# low-pass-fitler.net
KiCad netlist of a schematic drawn in Altium Designer
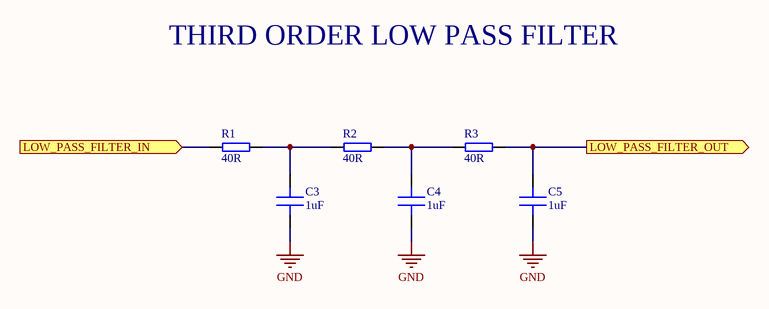
[diagram p0: low-pass-fitler.SchDoc]

(export (version "E")
  (design (tool "Eeschema 10.0.6"))
  (components
    (comp (ref "C3")
      (value "1uF")
      (footprint "C 0402")
      (description "MLCC Capacitor")
      (libsource (lib "Components") (part "Capacitor"))
    )
    (comp (ref "C4")
      (value "1uF")
      (footprint "C 0402")
      (description "MLCC Capacitor")
      (libsource (lib "Components") (part "Capacitor"))
    )
    (comp (ref "C5")
      (value "1uF")
      (footprint "C 0402")
      (description "MLCC Capacitor")
      (libsource (lib "Components") (part "Capacitor"))
    )
    (comp (ref "R1")
      (value "40R")
      (footprint "R 0402")
      (description "General pourpouse resistor")
      (libsource (lib "Components") (part "Resistor"))
    )
    (comp (ref "R2")
      (value "40R")
      (footprint "R 0402")
      (description "General pourpouse resistor")
      (libsource (lib "Components") (part "Resistor"))
    )
    (comp (ref "R3")
      (value "40R")
      (footprint "R 0402")
      (description "General pourpouse resistor")
      (libsource (lib "Components") (part "Resistor"))
    )
  )
  (nets
    (net (code "1") (name "/LOW_PASS_FILTER_IN") (class "Default")
      (node (ref "R1") (pin "1") (pinfunction "1_1") (pintype "passive"))
    )
    (net (code "2") (name "/LOW_PASS_FILTER_OUT") (class "Default")
      (node (ref "C5") (pin "1") (pinfunction "1_1") (pintype "passive"))
      (node (ref "R3") (pin "2") (pinfunction "2_2") (pintype "passive"))
    )
    (net (code "3") (name "GND") (class "Default")
      (node (ref "C3") (pin "2") (pinfunction "2_2") (pintype "passive"))
      (node (ref "C4") (pin "2") (pinfunction "2_2") (pintype "passive"))
      (node (ref "C5") (pin "2") (pinfunction "2_2") (pintype "passive"))
    )
    (net (code "4") (name "Net-(C3-Pad1)") (class "Default")
      (node (ref "C3") (pin "1") (pinfunction "1_1") (pintype "passive"))
      (node (ref "R1") (pin "2") (pinfunction "2_2") (pintype "passive"))
      (node (ref "R2") (pin "1") (pinfunction "1_1") (pintype "passive"))
    )
    (net (code "5") (name "Net-(C4-Pad1)") (class "Default")
      (node (ref "C4") (pin "1") (pinfunction "1_1") (pintype "passive"))
      (node (ref "R2") (pin "2") (pinfunction "2_2") (pintype "passive"))
      (node (ref "R3") (pin "1") (pinfunction "1_1") (pintype "passive"))
    )
  )
)
